# matriz_8x8.net
KiCad netlist of a schematic drawn in EAGLE
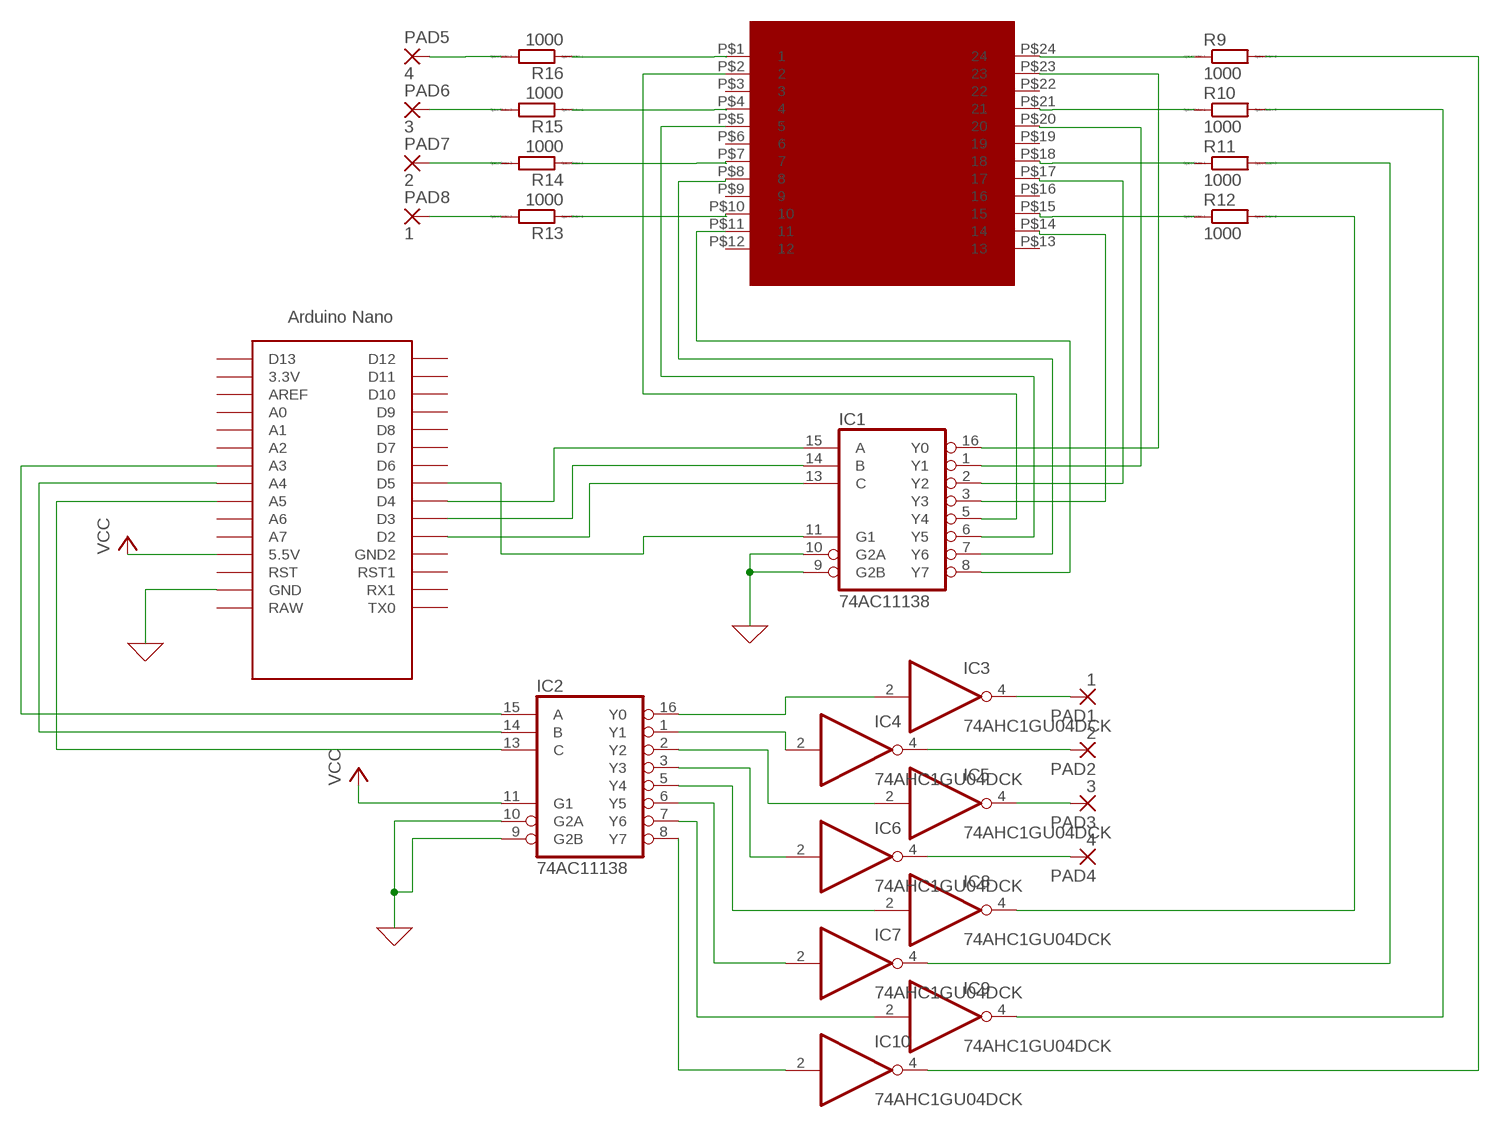
[diagram p0: schematic, sheet 1]

(export (version "E")
  (design (tool "Eeschema 10.0.6"))
  (components
    (comp (ref "IC1")
      (value "74AC11138")
      (footprint "eagle-import:DIL16")
      (libsource (lib "eagle-import") (part "74AC11138"))
    )
    (comp (ref "IC2")
      (value "74AC11138")
      (footprint "eagle-import:DIL16")
      (libsource (lib "eagle-import") (part "74AC11138"))
    )
    (comp (ref "IC3")
      (value "74AHC1GU04DCK")
      (footprint "eagle-import:SC70-5")
      (libsource (lib "eagle-import") (part "741GU04DCKAHC"))
    )
    (comp (ref "IC4")
      (value "74AHC1GU04DCK")
      (footprint "eagle-import:SC70-5")
      (libsource (lib "eagle-import") (part "741GU04DCKAHC"))
    )
    (comp (ref "IC5")
      (value "74AHC1GU04DCK")
      (footprint "eagle-import:SC70-5")
      (libsource (lib "eagle-import") (part "741GU04DCKAHC"))
    )
    (comp (ref "IC6")
      (value "74AHC1GU04DCK")
      (footprint "eagle-import:SC70-5")
      (libsource (lib "eagle-import") (part "741GU04DCKAHC"))
    )
    (comp (ref "IC7")
      (value "74AHC1GU04DCK")
      (footprint "eagle-import:SC70-5")
      (libsource (lib "eagle-import") (part "741GU04DCKAHC"))
    )
    (comp (ref "IC8")
      (value "74AHC1GU04DCK")
      (footprint "eagle-import:SC70-5")
      (libsource (lib "eagle-import") (part "741GU04DCKAHC"))
    )
    (comp (ref "IC9")
      (value "74AHC1GU04DCK")
      (footprint "eagle-import:SC70-5")
      (libsource (lib "eagle-import") (part "741GU04DCKAHC"))
    )
    (comp (ref "IC10")
      (value "74AHC1GU04DCK")
      (footprint "eagle-import:SC70-5")
      (libsource (lib "eagle-import") (part "741GU04DCKAHC"))
    )
    (comp (ref "PAD1")
      (value "1")
      (footprint "eagle-import:1,6_0,8")
      (libsource (lib "eagle-import") (part "1,6/0,8"))
    )
    (comp (ref "PAD2")
      (value "2")
      (footprint "eagle-import:1,6_0,8")
      (libsource (lib "eagle-import") (part "1,6/0,8"))
    )
    (comp (ref "PAD3")
      (value "3")
      (footprint "eagle-import:1,6_0,8")
      (libsource (lib "eagle-import") (part "1,6/0,8"))
    )
    (comp (ref "PAD4")
      (value "4")
      (footprint "eagle-import:1,6_0,8")
      (libsource (lib "eagle-import") (part "1,6/0,8"))
    )
    (comp (ref "PAD5")
      (value "4")
      (footprint "eagle-import:1,6_0,8")
      (libsource (lib "eagle-import") (part "1,6/0,8"))
    )
    (comp (ref "PAD6")
      (value "3")
      (footprint "eagle-import:1,6_0,8")
      (libsource (lib "eagle-import") (part "1,6/0,8"))
    )
    (comp (ref "PAD7")
      (value "2")
      (footprint "eagle-import:1,6_0,8")
      (libsource (lib "eagle-import") (part "1,6/0,8"))
    )
    (comp (ref "PAD8")
      (value "1")
      (footprint "eagle-import:1,6_0,8")
      (libsource (lib "eagle-import") (part "1,6/0,8"))
    )
    (comp (ref "R9")
      (value "1000")
      (footprint "eagle-import:0204_7")
      (libsource (lib "eagle-import") (part "R0204/7"))
    )
    (comp (ref "R10")
      (value "1000")
      (footprint "eagle-import:0204_7")
      (libsource (lib "eagle-import") (part "R0204/7"))
    )
    (comp (ref "R11")
      (value "1000")
      (footprint "eagle-import:0204_7")
      (libsource (lib "eagle-import") (part "R0204/7"))
    )
    (comp (ref "R12")
      (value "1000")
      (footprint "eagle-import:0204_7")
      (libsource (lib "eagle-import") (part "R0204/7"))
    )
    (comp (ref "R13")
      (value "1000")
      (footprint "eagle-import:0204_7")
      (libsource (lib "eagle-import") (part "R0204/7"))
    )
    (comp (ref "R14")
      (value "1000")
      (footprint "eagle-import:0204_7")
      (libsource (lib "eagle-import") (part "R0204/7"))
    )
    (comp (ref "R15")
      (value "1000")
      (footprint "eagle-import:0204_7")
      (libsource (lib "eagle-import") (part "R0204/7"))
    )
    (comp (ref "R16")
      (value "1000")
      (footprint "eagle-import:0204_7")
      (libsource (lib "eagle-import") (part "R0204/7"))
    )
    (comp (ref "U$1")
      (value "8X8_BI_COLOR_MATRIX")
      (footprint "eagle-import:8X8_BI_COLOR_MATRIX")
      (libsource (lib "eagle-import") (part "8X8_BI_COLOR_MATRIX"))
    )
    (comp (ref "U$2")
      (value "NANO")
      (footprint "eagle-import:NANO")
      (libsource (lib "eagle-import") (part "NANO"))
    )
  )
  (nets
    (net (code "1") (name "GND") (class "Default")
      (node (ref "IC1") (pin "10") (pinfunction "G2A_10") (pintype "input"))
      (node (ref "IC1") (pin "9") (pinfunction "G2B_9") (pintype "input"))
      (node (ref "IC2") (pin "10") (pinfunction "G2A_10") (pintype "input"))
      (node (ref "IC2") (pin "9") (pinfunction "G2B_9") (pintype "input"))
      (node (ref "U$2") (pin "GND") (pinfunction "GND_GND") (pintype "bidirectional"))
    )
    (net (code "2") (name "Net-(IC1A-A)") (class "Default")
      (node (ref "IC1") (pin "15") (pinfunction "A_15") (pintype "input"))
      (node (ref "U$2") (pin "D4") (pinfunction "D4_D4") (pintype "bidirectional"))
    )
    (net (code "3") (name "Net-(IC1A-B)") (class "Default")
      (node (ref "IC1") (pin "14") (pinfunction "B_14") (pintype "input"))
      (node (ref "U$2") (pin "D3") (pinfunction "D3_D3") (pintype "bidirectional"))
    )
    (net (code "4") (name "Net-(IC1A-C)") (class "Default")
      (node (ref "IC1") (pin "13") (pinfunction "C_13") (pintype "input"))
      (node (ref "U$2") (pin "D2") (pinfunction "D2_D2") (pintype "bidirectional"))
    )
    (net (code "5") (name "Net-(IC1A-G1)") (class "Default")
      (node (ref "IC1") (pin "11") (pinfunction "G1_11") (pintype "input"))
      (node (ref "U$2") (pin "D5") (pinfunction "D5_D5") (pintype "bidirectional"))
    )
    (net (code "6") (name "Net-(IC1A-Y0)") (class "Default")
      (node (ref "IC1") (pin "16") (pinfunction "Y0_16") (pintype "output"))
      (node (ref "U$1") (pin "P$23") (pinfunction "23_P$23") (pintype "bidirectional"))
    )
    (net (code "7") (name "Net-(IC1A-Y1)") (class "Default")
      (node (ref "IC1") (pin "1") (pinfunction "Y1_1") (pintype "output"))
      (node (ref "U$1") (pin "P$20") (pinfunction "20_P$20") (pintype "bidirectional"))
    )
    (net (code "8") (name "Net-(IC1A-Y2)") (class "Default")
      (node (ref "IC1") (pin "2") (pinfunction "Y2_2") (pintype "output"))
      (node (ref "U$1") (pin "P$17") (pinfunction "17_P$17") (pintype "bidirectional"))
    )
    (net (code "9") (name "Net-(IC1A-Y3)") (class "Default")
      (node (ref "IC1") (pin "3") (pinfunction "Y3_3") (pintype "output"))
      (node (ref "U$1") (pin "P$14") (pinfunction "14_P$14") (pintype "bidirectional"))
    )
    (net (code "10") (name "Net-(IC1A-Y4)") (class "Default")
      (node (ref "IC1") (pin "5") (pinfunction "Y4_5") (pintype "output"))
      (node (ref "U$1") (pin "P$2") (pinfunction "2_P$2") (pintype "bidirectional"))
    )
    (net (code "11") (name "Net-(IC1A-Y5)") (class "Default")
      (node (ref "IC1") (pin "6") (pinfunction "Y5_6") (pintype "output"))
      (node (ref "U$1") (pin "P$5") (pinfunction "5_P$5") (pintype "bidirectional"))
    )
    (net (code "12") (name "Net-(IC1A-Y6)") (class "Default")
      (node (ref "IC1") (pin "7") (pinfunction "Y6_7") (pintype "output"))
      (node (ref "U$1") (pin "P$8") (pinfunction "8_P$8") (pintype "bidirectional"))
    )
    (net (code "13") (name "Net-(IC1A-Y7)") (class "Default")
      (node (ref "IC1") (pin "8") (pinfunction "Y7_8") (pintype "output"))
      (node (ref "U$1") (pin "P$11") (pinfunction "11_P$11") (pintype "bidirectional"))
    )
    (net (code "14") (name "Net-(IC2A-A)") (class "Default")
      (node (ref "IC2") (pin "15") (pinfunction "A_15") (pintype "input"))
      (node (ref "U$2") (pin "A3") (pinfunction "A3_A3") (pintype "bidirectional"))
    )
    (net (code "15") (name "Net-(IC2A-B)") (class "Default")
      (node (ref "IC2") (pin "14") (pinfunction "B_14") (pintype "input"))
      (node (ref "U$2") (pin "A4") (pinfunction "A4_A4") (pintype "bidirectional"))
    )
    (net (code "16") (name "Net-(IC2A-C)") (class "Default")
      (node (ref "IC2") (pin "13") (pinfunction "C_13") (pintype "input"))
      (node (ref "U$2") (pin "A5") (pinfunction "A5_A5") (pintype "bidirectional"))
    )
    (net (code "17") (name "Net-(IC2A-Y0)") (class "Default")
      (node (ref "IC2") (pin "16") (pinfunction "Y0_16") (pintype "output"))
      (node (ref "IC3") (pin "2") (pinfunction "I_2") (pintype "input"))
    )
    (net (code "18") (name "Net-(IC2A-Y1)") (class "Default")
      (node (ref "IC2") (pin "1") (pinfunction "Y1_1") (pintype "output"))
      (node (ref "IC4") (pin "2") (pinfunction "I_2") (pintype "input"))
    )
    (net (code "19") (name "Net-(IC2A-Y2)") (class "Default")
      (node (ref "IC2") (pin "2") (pinfunction "Y2_2") (pintype "output"))
      (node (ref "IC5") (pin "2") (pinfunction "I_2") (pintype "input"))
    )
    (net (code "20") (name "Net-(IC2A-Y3)") (class "Default")
      (node (ref "IC2") (pin "3") (pinfunction "Y3_3") (pintype "output"))
      (node (ref "IC6") (pin "2") (pinfunction "I_2") (pintype "input"))
    )
    (net (code "21") (name "Net-(IC2A-Y4)") (class "Default")
      (node (ref "IC2") (pin "5") (pinfunction "Y4_5") (pintype "output"))
      (node (ref "IC8") (pin "2") (pinfunction "I_2") (pintype "input"))
    )
    (net (code "22") (name "Net-(IC2A-Y5)") (class "Default")
      (node (ref "IC2") (pin "6") (pinfunction "Y5_6") (pintype "output"))
      (node (ref "IC7") (pin "2") (pinfunction "I_2") (pintype "input"))
    )
    (net (code "23") (name "Net-(IC2A-Y6)") (class "Default")
      (node (ref "IC2") (pin "7") (pinfunction "Y6_7") (pintype "output"))
      (node (ref "IC9") (pin "2") (pinfunction "I_2") (pintype "input"))
    )
    (net (code "24") (name "Net-(IC3A-O)") (class "Default")
      (node (ref "IC3") (pin "4") (pinfunction "O_4") (pintype "output"))
      (node (ref "PAD1") (pin "1") (pinfunction "P_1") (pintype "passive"))
    )
    (net (code "25") (name "Net-(IC4A-O)") (class "Default")
      (node (ref "IC4") (pin "4") (pinfunction "O_4") (pintype "output"))
      (node (ref "PAD2") (pin "1") (pinfunction "P_1") (pintype "passive"))
    )
    (net (code "26") (name "Net-(IC5A-O)") (class "Default")
      (node (ref "IC5") (pin "4") (pinfunction "O_4") (pintype "output"))
      (node (ref "PAD3") (pin "1") (pinfunction "P_1") (pintype "passive"))
    )
    (net (code "27") (name "Net-(IC6A-O)") (class "Default")
      (node (ref "IC6") (pin "4") (pinfunction "O_4") (pintype "output"))
      (node (ref "PAD4") (pin "1") (pinfunction "P_1") (pintype "passive"))
    )
    (net (code "28") (name "Net-(IC7A-O)") (class "Default")
      (node (ref "IC7") (pin "4") (pinfunction "O_4") (pintype "output"))
      (node (ref "R11") (pin "2") (pinfunction "2_2") (pintype "passive"))
    )
    (net (code "29") (name "Net-(IC8A-O)") (class "Default")
      (node (ref "IC8") (pin "4") (pinfunction "O_4") (pintype "output"))
      (node (ref "R12") (pin "2") (pinfunction "2_2") (pintype "passive"))
    )
    (net (code "30") (name "Net-(IC9A-O)") (class "Default")
      (node (ref "IC9") (pin "4") (pinfunction "O_4") (pintype "output"))
      (node (ref "R10") (pin "2") (pinfunction "2_2") (pintype "passive"))
    )
    (net (code "31") (name "Net-(IC10A-I)") (class "Default")
      (node (ref "IC10") (pin "2") (pinfunction "I_2") (pintype "input"))
      (node (ref "IC2") (pin "8") (pinfunction "Y7_8") (pintype "output"))
    )
    (net (code "32") (name "Net-(IC10A-O)") (class "Default")
      (node (ref "IC10") (pin "4") (pinfunction "O_4") (pintype "output"))
      (node (ref "R9") (pin "2") (pinfunction "2_2") (pintype "passive"))
    )
    (net (code "33") (name "Net-(PAD5-P)") (class "Default")
      (node (ref "PAD5") (pin "1") (pinfunction "P_1") (pintype "passive"))
      (node (ref "R16") (pin "2") (pinfunction "2_2") (pintype "passive"))
    )
    (net (code "34") (name "Net-(PAD6-P)") (class "Default")
      (node (ref "PAD6") (pin "1") (pinfunction "P_1") (pintype "passive"))
      (node (ref "R15") (pin "2") (pinfunction "2_2") (pintype "passive"))
    )
    (net (code "35") (name "Net-(PAD7-P)") (class "Default")
      (node (ref "PAD7") (pin "1") (pinfunction "P_1") (pintype "passive"))
      (node (ref "R14") (pin "2") (pinfunction "2_2") (pintype "passive"))
    )
    (net (code "36") (name "Net-(PAD8-P)") (class "Default")
      (node (ref "PAD8") (pin "1") (pinfunction "P_1") (pintype "passive"))
      (node (ref "R13") (pin "2") (pinfunction "2_2") (pintype "passive"))
    )
    (net (code "37") (name "Net-(U$1-1)") (class "Default")
      (node (ref "R16") (pin "1") (pinfunction "1_1") (pintype "passive"))
      (node (ref "U$1") (pin "P$1") (pinfunction "1_P$1") (pintype "bidirectional"))
    )
    (net (code "38") (name "Net-(U$1-4)") (class "Default")
      (node (ref "R15") (pin "1") (pinfunction "1_1") (pintype "passive"))
      (node (ref "U$1") (pin "P$4") (pinfunction "4_P$4") (pintype "bidirectional"))
    )
    (net (code "39") (name "Net-(U$1-7)") (class "Default")
      (node (ref "R14") (pin "1") (pinfunction "1_1") (pintype "passive"))
      (node (ref "U$1") (pin "P$7") (pinfunction "7_P$7") (pintype "bidirectional"))
    )
    (net (code "40") (name "Net-(U$1-10)") (class "Default")
      (node (ref "R13") (pin "1") (pinfunction "1_1") (pintype "passive"))
      (node (ref "U$1") (pin "P$10") (pinfunction "10_P$10") (pintype "bidirectional"))
    )
    (net (code "41") (name "Net-(U$1-15)") (class "Default")
      (node (ref "R12") (pin "1") (pinfunction "1_1") (pintype "passive"))
      (node (ref "U$1") (pin "P$15") (pinfunction "15_P$15") (pintype "bidirectional"))
    )
    (net (code "42") (name "Net-(U$1-18)") (class "Default")
      (node (ref "R11") (pin "1") (pinfunction "1_1") (pintype "passive"))
      (node (ref "U$1") (pin "P$18") (pinfunction "18_P$18") (pintype "bidirectional"))
    )
    (net (code "43") (name "Net-(U$1-21)") (class "Default")
      (node (ref "R10") (pin "1") (pinfunction "1_1") (pintype "passive"))
      (node (ref "U$1") (pin "P$21") (pinfunction "21_P$21") (pintype "bidirectional"))
    )
    (net (code "44") (name "Net-(U$1-24)") (class "Default")
      (node (ref "R9") (pin "1") (pinfunction "1_1") (pintype "passive"))
      (node (ref "U$1") (pin "P$24") (pinfunction "24_P$24") (pintype "bidirectional"))
    )
    (net (code "45") (name "VCC") (class "Default")
      (node (ref "IC2") (pin "11") (pinfunction "G1_11") (pintype "input"))
      (node (ref "U$2") (pin "5V") (pinfunction "5.5V_5V") (pintype "bidirectional"))
    )
    (net (code "46") (name "unconnected-(U$1-3-PadP$3)") (class "Default")
      (node (ref "U$1") (pin "P$3") (pinfunction "3_P$3") (pintype "bidirectional"))
    )
    (net (code "47") (name "unconnected-(U$1-6-PadP$6)") (class "Default")
      (node (ref "U$1") (pin "P$6") (pinfunction "6_P$6") (pintype "bidirectional"))
    )
    (net (code "48") (name "unconnected-(U$1-9-PadP$9)") (class "Default")
      (node (ref "U$1") (pin "P$9") (pinfunction "9_P$9") (pintype "bidirectional"))
    )
    (net (code "49") (name "unconnected-(U$1-12-PadP$12)") (class "Default")
      (node (ref "U$1") (pin "P$12") (pinfunction "12_P$12") (pintype "bidirectional"))
    )
    (net (code "50") (name "unconnected-(U$1-13-PadP$13)") (class "Default")
      (node (ref "U$1") (pin "P$13") (pinfunction "13_P$13") (pintype "bidirectional"))
    )
    (net (code "51") (name "unconnected-(U$1-16-PadP$16)") (class "Default")
      (node (ref "U$1") (pin "P$16") (pinfunction "16_P$16") (pintype "bidirectional"))
    )
    (net (code "52") (name "unconnected-(U$1-19-PadP$19)") (class "Default")
      (node (ref "U$1") (pin "P$19") (pinfunction "19_P$19") (pintype "bidirectional"))
    )
    (net (code "53") (name "unconnected-(U$1-22-PadP$22)") (class "Default")
      (node (ref "U$1") (pin "P$22") (pinfunction "22_P$22") (pintype "bidirectional"))
    )
    (net (code "54") (name "unconnected-(U$2-GND2-PadGND1)") (class "Default")
      (node (ref "U$2") (pin "GND1") (pinfunction "GND2_GND1") (pintype "bidirectional"))
    )
    (net (code "55") (name "unconnected-(U$2-Pad3.3V)") (class "Default")
      (node (ref "U$2") (pin "3.3V") (pinfunction "3.3V_3.3V") (pintype "bidirectional"))
    )
    (net (code "56") (name "unconnected-(U$2-PadA0)") (class "Default")
      (node (ref "U$2") (pin "A0") (pinfunction "A0_A0") (pintype "bidirectional"))
    )
    (net (code "57") (name "unconnected-(U$2-PadA1)") (class "Default")
      (node (ref "U$2") (pin "A1") (pinfunction "A1_A1") (pintype "bidirectional"))
    )
    (net (code "58") (name "unconnected-(U$2-PadA2)") (class "Default")
      (node (ref "U$2") (pin "A2") (pinfunction "A2_A2") (pintype "bidirectional"))
    )
    (net (code "59") (name "unconnected-(U$2-PadA6)") (class "Default")
      (node (ref "U$2") (pin "A6") (pinfunction "A6_A6") (pintype "bidirectional"))
    )
    (net (code "60") (name "unconnected-(U$2-PadA7)") (class "Default")
      (node (ref "U$2") (pin "A7") (pinfunction "A7_A7") (pintype "bidirectional"))
    )
    (net (code "61") (name "unconnected-(U$2-PadAREF)") (class "Default")
      (node (ref "U$2") (pin "AREF") (pinfunction "AREF_AREF") (pintype "bidirectional"))
    )
    (net (code "62") (name "unconnected-(U$2-PadD6)") (class "Default")
      (node (ref "U$2") (pin "D6") (pinfunction "D6_D6") (pintype "bidirectional"))
    )
    (net (code "63") (name "unconnected-(U$2-PadD7)") (class "Default")
      (node (ref "U$2") (pin "D7") (pinfunction "D7_D7") (pintype "bidirectional"))
    )
    (net (code "64") (name "unconnected-(U$2-PadD8)") (class "Default")
      (node (ref "U$2") (pin "D8") (pinfunction "D8_D8") (pintype "bidirectional"))
    )
    (net (code "65") (name "unconnected-(U$2-PadD9)") (class "Default")
      (node (ref "U$2") (pin "D9") (pinfunction "D9_D9") (pintype "bidirectional"))
    )
    (net (code "66") (name "unconnected-(U$2-PadD10)") (class "Default")
      (node (ref "U$2") (pin "D10") (pinfunction "D10_D10") (pintype "bidirectional"))
    )
    (net (code "67") (name "unconnected-(U$2-PadD11)") (class "Default")
      (node (ref "U$2") (pin "D11") (pinfunction "D11_D11") (pintype "bidirectional"))
    )
    (net (code "68") (name "unconnected-(U$2-PadD12)") (class "Default")
      (node (ref "U$2") (pin "D12") (pinfunction "D12_D12") (pintype "bidirectional"))
    )
    (net (code "69") (name "unconnected-(U$2-PadD13)") (class "Default")
      (node (ref "U$2") (pin "D13") (pinfunction "D13_D13") (pintype "bidirectional"))
    )
    (net (code "70") (name "unconnected-(U$2-PadICSP1)") (class "Default")
      (node (ref "U$2") (pin "ICSP1") (pinfunction "ICSP1_ICSP1") (pintype "bidirectional"))
    )
    (net (code "71") (name "unconnected-(U$2-PadICSP2)") (class "Default")
      (node (ref "U$2") (pin "ICSP2") (pinfunction "ICSP2_ICSP2") (pintype "bidirectional"))
    )
    (net (code "72") (name "unconnected-(U$2-PadICSP3)") (class "Default")
      (node (ref "U$2") (pin "ICSP3") (pinfunction "ICSP3_ICSP3") (pintype "bidirectional"))
    )
    (net (code "73") (name "unconnected-(U$2-PadICSP4)") (class "Default")
      (node (ref "U$2") (pin "ICSP4") (pinfunction "ICSP4_ICSP4") (pintype "bidirectional"))
    )
    (net (code "74") (name "unconnected-(U$2-PadICSP5)") (class "Default")
      (node (ref "U$2") (pin "ICSP5") (pinfunction "ICSP5_ICSP5") (pintype "bidirectional"))
    )
    (net (code "75") (name "unconnected-(U$2-PadICSP6)") (class "Default")
      (node (ref "U$2") (pin "ICSP6") (pinfunction "ICSP6_ICSP6") (pintype "bidirectional"))
    )
    (net (code "76") (name "unconnected-(U$2-PadRAW)") (class "Default")
      (node (ref "U$2") (pin "RAW") (pinfunction "RAW_RAW") (pintype "bidirectional"))
    )
    (net (code "77") (name "unconnected-(U$2-PadRST)") (class "Default")
      (node (ref "U$2") (pin "RST") (pinfunction "RST_RST") (pintype "bidirectional"))
    )
    (net (code "78") (name "unconnected-(U$2-PadRST1)") (class "Default")
      (node (ref "U$2") (pin "RST1") (pinfunction "RST1_RST1") (pintype "bidirectional"))
    )
    (net (code "79") (name "unconnected-(U$2-PadRX1)") (class "Default")
      (node (ref "U$2") (pin "RX1") (pinfunction "RX1_RX1") (pintype "bidirectional"))
    )
    (net (code "80") (name "unconnected-(U$2-PadTX0)") (class "Default")
      (node (ref "U$2") (pin "TX0") (pinfunction "TX0_TX0") (pintype "bidirectional"))
    )
  )
)
